# M1713A.net
KiCad netlist of a schematic drawn in EAGLE
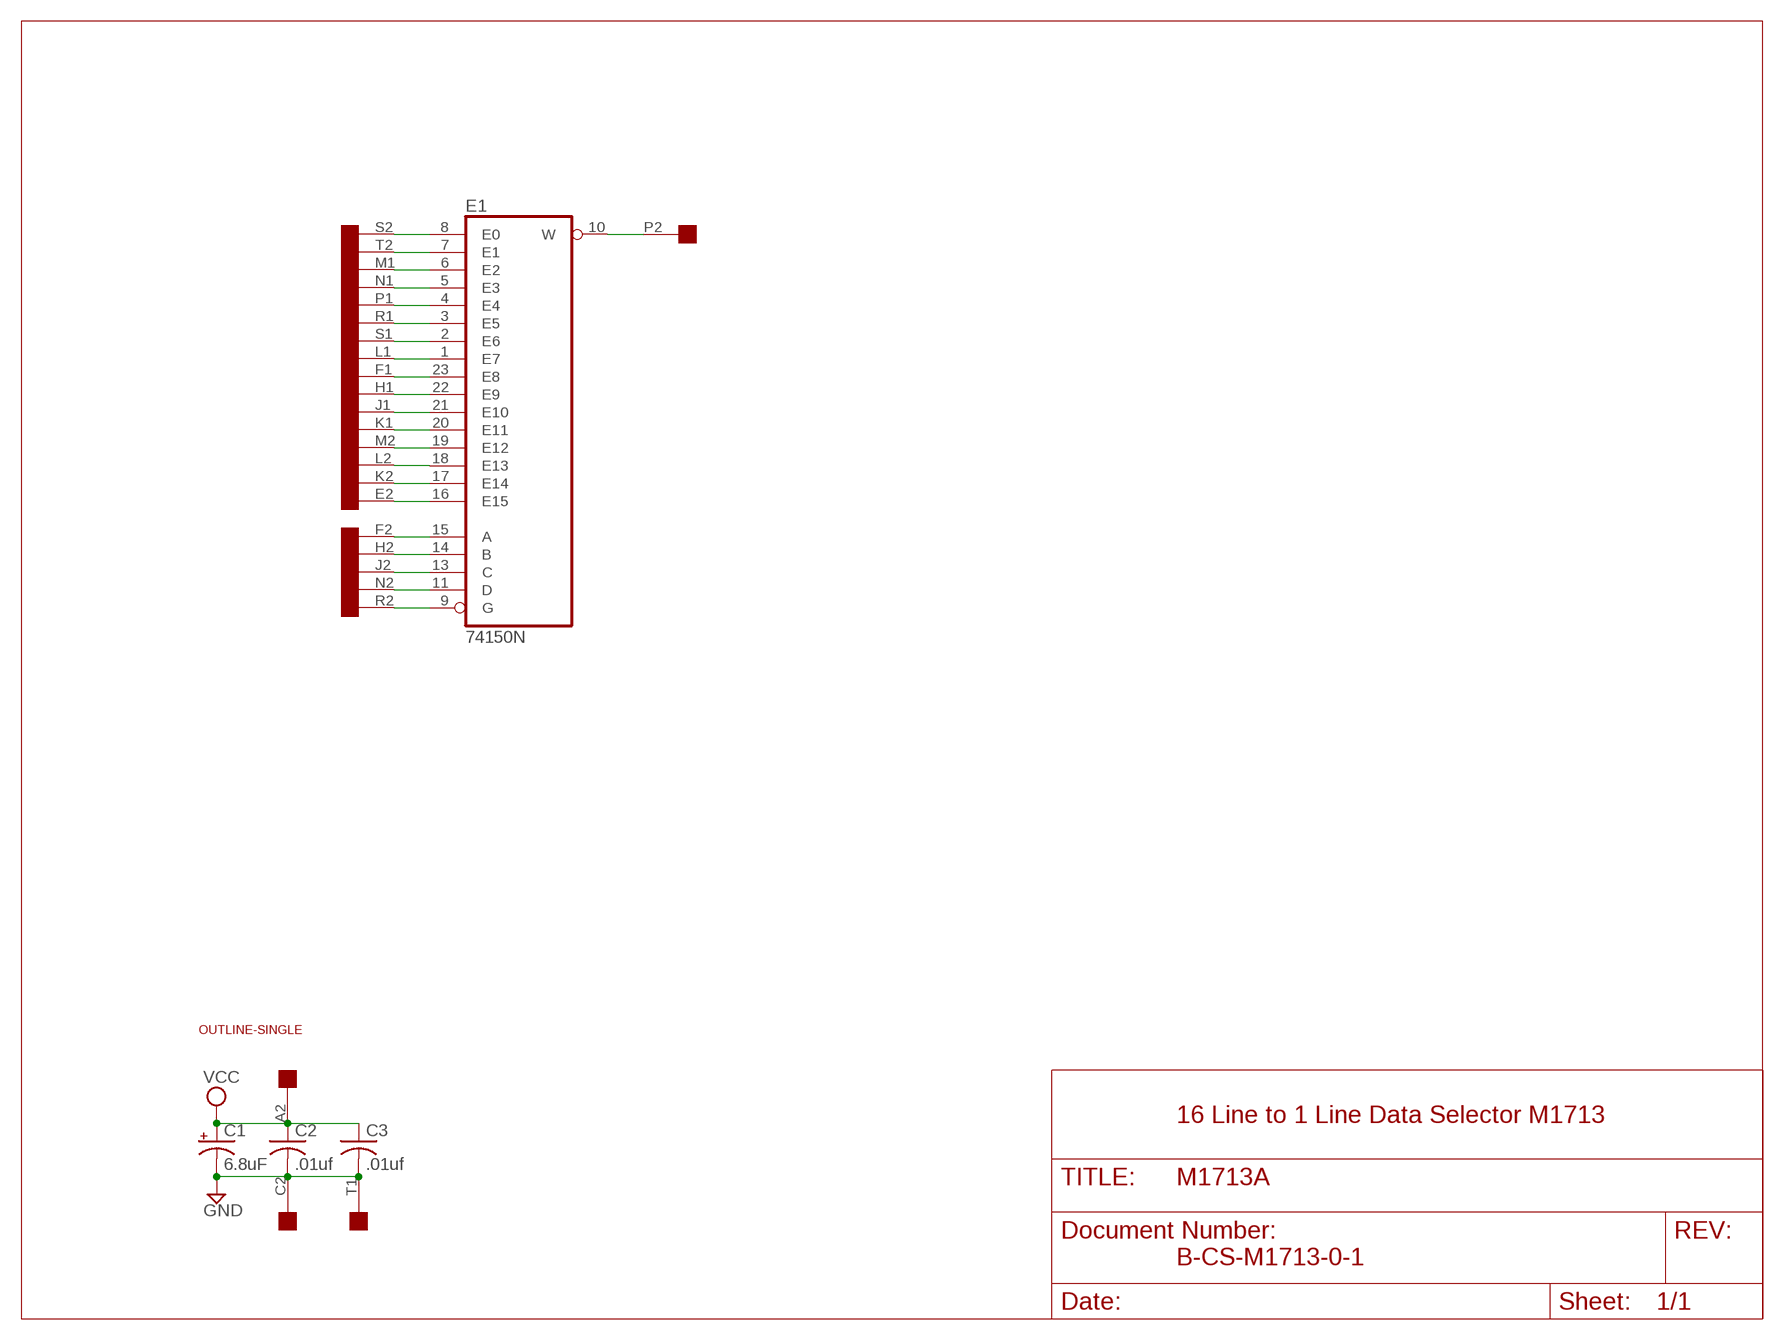
[diagram p0: schematic, sheet 1]

(export (version "E")
  (design (tool "Eeschema 10.0.6"))
  (components
    (comp (ref "C1")
      (value "6.8uF")
      (footprint "eagle-import:E22-6")
      (libsource (lib "eagle-import") (part "CPOL-USE22-6AXIAL"))
    )
    (comp (ref "C2")
      (value ".01uf")
      (footprint "eagle-import:C050-025X075")
      (libsource (lib "eagle-import") (part "C-US050-025X075"))
    )
    (comp (ref "C3")
      (value ".01uf")
      (footprint "eagle-import:C050-025X075")
      (libsource (lib "eagle-import") (part "C-US050-025X075"))
    )
    (comp (ref "E1")
      (value "74150N")
      (footprint "eagle-import:DIL24-6")
      (libsource (lib "eagle-import") (part "74150N"))
    )
    (comp (ref "U$1")
      (value "OUTLINE-SINGLE")
      (footprint "eagle-import:SINGLE")
      (libsource (lib "eagle-import") (part "OUTLINE-SINGLE"))
    )
    (comp (ref "U$2")
      (value "EDGE-2CONNECTOR")
      (footprint "eagle-import:EDGE-CON2")
      (libsource (lib "eagle-import") (part "EDGE-2CONNECTOR"))
    )
  )
  (nets
    (net (code "1") (name "GND") (class "Default")
      (node (ref "C1") (pin "-") (pinfunction "-_-") (pintype "passive"))
      (node (ref "C2") (pin "2") (pinfunction "2_2") (pintype "passive"))
      (node (ref "C3") (pin "2") (pinfunction "2_2") (pintype "passive"))
      (node (ref "U$2") (pin "C2") (pinfunction "1_C2") (pintype "bidirectional"))
      (node (ref "U$2") (pin "T1") (pinfunction "1_T1") (pintype "bidirectional"))
    )
    (net (code "2") (name "Net-(E1A-A)") (class "Default")
      (node (ref "E1") (pin "15") (pinfunction "A_15") (pintype "input"))
      (node (ref "U$2") (pin "F2") (pinfunction "1_F2") (pintype "bidirectional"))
    )
    (net (code "3") (name "Net-(E1A-B)") (class "Default")
      (node (ref "E1") (pin "14") (pinfunction "B_14") (pintype "input"))
      (node (ref "U$2") (pin "H2") (pinfunction "1_H2") (pintype "bidirectional"))
    )
    (net (code "4") (name "Net-(E1A-C)") (class "Default")
      (node (ref "E1") (pin "13") (pinfunction "C_13") (pintype "input"))
      (node (ref "U$2") (pin "J2") (pinfunction "1_J2") (pintype "bidirectional"))
    )
    (net (code "5") (name "Net-(E1A-D)") (class "Default")
      (node (ref "E1") (pin "11") (pinfunction "D_11") (pintype "input"))
      (node (ref "U$2") (pin "N2") (pinfunction "1_N2") (pintype "bidirectional"))
    )
    (net (code "6") (name "Net-(E1A-E0)") (class "Default")
      (node (ref "E1") (pin "8") (pinfunction "E0_8") (pintype "input"))
      (node (ref "U$2") (pin "S2") (pinfunction "1_S2") (pintype "bidirectional"))
    )
    (net (code "7") (name "Net-(E1A-E1)") (class "Default")
      (node (ref "E1") (pin "7") (pinfunction "E1_7") (pintype "input"))
      (node (ref "U$2") (pin "T2") (pinfunction "1_T2") (pintype "bidirectional"))
    )
    (net (code "8") (name "Net-(E1A-E2)") (class "Default")
      (node (ref "E1") (pin "6") (pinfunction "E2_6") (pintype "input"))
      (node (ref "U$2") (pin "M1") (pinfunction "1_M1") (pintype "bidirectional"))
    )
    (net (code "9") (name "Net-(E1A-E3)") (class "Default")
      (node (ref "E1") (pin "5") (pinfunction "E3_5") (pintype "input"))
      (node (ref "U$2") (pin "N1") (pinfunction "1_N1") (pintype "bidirectional"))
    )
    (net (code "10") (name "Net-(E1A-E4)") (class "Default")
      (node (ref "E1") (pin "4") (pinfunction "E4_4") (pintype "input"))
      (node (ref "U$2") (pin "P1") (pinfunction "1_P1") (pintype "bidirectional"))
    )
    (net (code "11") (name "Net-(E1A-E5)") (class "Default")
      (node (ref "E1") (pin "3") (pinfunction "E5_3") (pintype "input"))
      (node (ref "U$2") (pin "R1") (pinfunction "1_R1") (pintype "bidirectional"))
    )
    (net (code "12") (name "Net-(E1A-E6)") (class "Default")
      (node (ref "E1") (pin "2") (pinfunction "E6_2") (pintype "input"))
      (node (ref "U$2") (pin "S1") (pinfunction "1_S1") (pintype "bidirectional"))
    )
    (net (code "13") (name "Net-(E1A-E7)") (class "Default")
      (node (ref "E1") (pin "1") (pinfunction "E7_1") (pintype "input"))
      (node (ref "U$2") (pin "L1") (pinfunction "1_L1") (pintype "bidirectional"))
    )
    (net (code "14") (name "Net-(E1A-E8)") (class "Default")
      (node (ref "E1") (pin "23") (pinfunction "E8_23") (pintype "input"))
      (node (ref "U$2") (pin "F1") (pinfunction "1_F1") (pintype "bidirectional"))
    )
    (net (code "15") (name "Net-(E1A-E9)") (class "Default")
      (node (ref "E1") (pin "22") (pinfunction "E9_22") (pintype "input"))
      (node (ref "U$2") (pin "H1") (pinfunction "1_H1") (pintype "bidirectional"))
    )
    (net (code "16") (name "Net-(E1A-E10)") (class "Default")
      (node (ref "E1") (pin "21") (pinfunction "E10_21") (pintype "input"))
      (node (ref "U$2") (pin "J1") (pinfunction "1_J1") (pintype "bidirectional"))
    )
    (net (code "17") (name "Net-(E1A-E11)") (class "Default")
      (node (ref "E1") (pin "20") (pinfunction "E11_20") (pintype "input"))
      (node (ref "U$2") (pin "K1") (pinfunction "1_K1") (pintype "bidirectional"))
    )
    (net (code "18") (name "Net-(E1A-E12)") (class "Default")
      (node (ref "E1") (pin "19") (pinfunction "E12_19") (pintype "input"))
      (node (ref "U$2") (pin "M2") (pinfunction "1_M2") (pintype "bidirectional"))
    )
    (net (code "19") (name "Net-(E1A-E13)") (class "Default")
      (node (ref "E1") (pin "18") (pinfunction "E13_18") (pintype "input"))
      (node (ref "U$2") (pin "L2") (pinfunction "1_L2") (pintype "bidirectional"))
    )
    (net (code "20") (name "Net-(E1A-E14)") (class "Default")
      (node (ref "E1") (pin "17") (pinfunction "E14_17") (pintype "input"))
      (node (ref "U$2") (pin "K2") (pinfunction "1_K2") (pintype "bidirectional"))
    )
    (net (code "21") (name "Net-(E1A-E15)") (class "Default")
      (node (ref "E1") (pin "16") (pinfunction "E15_16") (pintype "input"))
      (node (ref "U$2") (pin "E2") (pinfunction "1_E2") (pintype "bidirectional"))
    )
    (net (code "22") (name "Net-(E1A-G)") (class "Default")
      (node (ref "E1") (pin "9") (pinfunction "G_9") (pintype "input"))
      (node (ref "U$2") (pin "R2") (pinfunction "1_R2") (pintype "bidirectional"))
    )
    (net (code "23") (name "Net-(E1A-W)") (class "Default")
      (node (ref "E1") (pin "10") (pinfunction "W_10") (pintype "output"))
      (node (ref "U$2") (pin "P2") (pinfunction "1_P2") (pintype "bidirectional"))
    )
    (net (code "24") (name "VCC") (class "Default")
      (node (ref "C1") (pin "+") (pinfunction "+_+") (pintype "passive"))
      (node (ref "C2") (pin "1") (pinfunction "1_1") (pintype "passive"))
      (node (ref "C3") (pin "1") (pinfunction "1_1") (pintype "passive"))
      (node (ref "U$2") (pin "A2") (pinfunction "1_A2") (pintype "bidirectional"))
    )
  )
)
